# ADC.net
KiCad netlist of a schematic drawn in Altium Designer
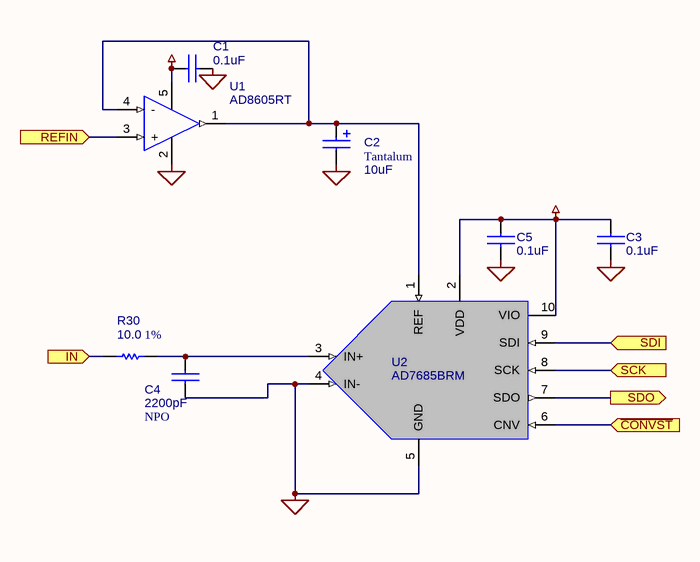
[diagram p0: ADC.SCHDOC]

(export (version "E")
  (design (tool "Eeschema 10.0.6"))
  (components
    (comp (ref "C1")
      (value "0.1uF")
      (footprint "0603")
      (description "Standard Capacitor")
      (fields (field (name "Comment") "CAPACITOR"))
      (libsource (lib "parts") (part "CAPACITOR"))
    )
    (comp (ref "C2")
      (value "10uF")
      (footprint "3216")
      (description "Standard Capacitor")
      (fields (field (name "TYPE") "Tantalum") (field (name "Comment") "Tantalum"))
      (libsource (lib "parts") (part "POLCAP"))
    )
    (comp (ref "C3")
      (value "0.1uF")
      (footprint "0603")
      (description "Standard Capacitor")
      (fields (field (name "Comment") "CAPACITOR"))
      (libsource (lib "parts") (part "CAPACITOR"))
    )
    (comp (ref "C4")
      (value "2200pF")
      (footprint "0603")
      (description "Standard Capacitor")
      (fields (field (name "TYPE") "NPO") (field (name "Comment") "CAPACITOR"))
      (libsource (lib "parts") (part "CAPACITOR"))
    )
    (comp (ref "C5")
      (value "0.1uF")
      (footprint "0603")
      (description "Standard Capacitor")
      (fields (field (name "Comment") "CAPACITOR"))
      (libsource (lib "parts") (part "CAPACITOR"))
    )
    (comp (ref "R30")
      (value "10.0")
      (footprint "0603")
      (description "Standard Passive Resistor")
      (fields (field (name "TOLERANCE") "1%") (field (name "Comment") "RESISTOR"))
      (libsource (lib "parts") (part "RESISTOR"))
    )
    (comp (ref "U1")
      (value "AD8605RT")
      (footprint "SOT-5")
      (description "Analog Devices Precision Low Noise CMOS Rail-to-Rail Input/Output Operational Amplifier")
      (libsource (lib "parts") (part "AD8605RT"))
    )
    (comp (ref "U2")
      (value "AD7685BRM")
      (footprint "AD RM-10")
      (description "AD 16-bit 250 kSPS ADC")
      (libsource (lib "parts") (part "AD7685"))
    )
  )
  (nets
    (net (code "1") (name "/IN") (class "Default") (node (ref "R30") (pin "1") (pintype "passive")))
    (net (code "2") (name "/REFIN") (class "Default")
      (node (ref "U1") (pin "3") (pinfunction "+_3") (pintype "input"))
    )
    (net (code "3") (name "/SCK") (class "Default")
      (node (ref "U2") (pin "8") (pinfunction "SCK_8") (pintype "input"))
    )
    (net (code "4") (name "/SDI") (class "Default")
      (node (ref "U2") (pin "9") (pinfunction "SDI_9") (pintype "input"))
    )
    (net (code "5") (name "/SDO") (class "Default")
      (node (ref "U2") (pin "7") (pinfunction "SDO_7") (pintype "output"))
    )
    (net (code "6") (name "/~{CONVST}") (class "Default")
      (node (ref "U2") (pin "6") (pinfunction "CNV_6") (pintype "input"))
    )
    (net (code "7") (name "AGND") (class "Default")
      (node (ref "C1") (pin "2") (pintype "passive"))
      (node (ref "C2") (pin "2") (pintype "passive"))
      (node (ref "C3") (pin "1") (pintype "passive"))
      (node (ref "C4") (pin "1") (pintype "passive"))
      (node (ref "C5") (pin "1") (pintype "passive"))
      (node (ref "U1") (pin "2") (pinfunction "-Vs_2") (pintype "power_in"))
      (node (ref "U2") (pin "4") (pinfunction "IN-_4") (pintype "input"))
      (node (ref "U2") (pin "5") (pinfunction "GND_5") (pintype "power_in"))
    )
    (net (code "8") (name "AVDD") (class "Default")
      (node (ref "C1") (pin "1") (pintype "passive"))
      (node (ref "C3") (pin "2") (pintype "passive"))
      (node (ref "C5") (pin "2") (pintype "passive"))
      (node (ref "U1") (pin "5") (pinfunction "+Vs_5") (pintype "power_in"))
      (node (ref "U2") (pin "10") (pinfunction "VIO_10") (pintype "power_in"))
      (node (ref "U2") (pin "2") (pinfunction "VDD_2") (pintype "power_in"))
    )
    (net (code "9") (name "Net-(U1--)") (class "Default")
      (node (ref "C2") (pin "1") (pintype "passive"))
      (node (ref "U1") (pin "1") (pinfunction "Out_1") (pintype "output"))
      (node (ref "U1") (pin "4") (pinfunction "-_4") (pintype "input"))
      (node (ref "U2") (pin "1") (pinfunction "REF_1") (pintype "input"))
    )
    (net (code "10") (name "Net-(U2-IN+)") (class "Default")
      (node (ref "C4") (pin "2") (pintype "passive"))
      (node (ref "R30") (pin "2") (pintype "passive"))
      (node (ref "U2") (pin "3") (pinfunction "IN+_3") (pintype "input"))
    )
  )
)
